# Neg5V0Reg.net
KiCad netlist of a schematic drawn in Altium Designer
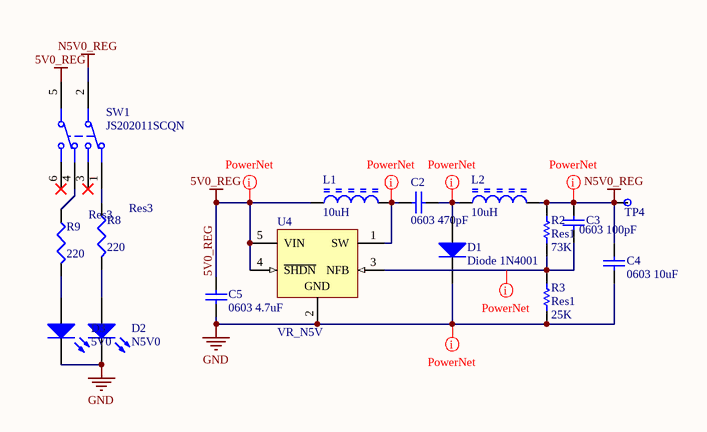
[diagram p0: Neg5V0Reg.SchDoc]

(export (version "E")
  (design (tool "Eeschema 10.0.6"))
  (components
    (comp (ref "C2")
      (value "0603 470pF")
      (footprint "CAPC1608X90X35LL10T15")
      (fields (field (name "PART NUMBER") "GRM188R61E475KE11D") (field (name "MANUFACTURER") "Murata"))
      (libsource (lib "Altium Content Vault") (part "CAP"))
    )
    (comp (ref "C3")
      (value "0603 100pF")
      (footprint "CAPC1608X90X35LL10T15")
      (fields (field (name "PART NUMBER") "GRM188R61E475KE11D") (field (name "MANUFACTURER") "Murata"))
      (libsource (lib "Altium Content Vault") (part "CAP"))
    )
    (comp (ref "C4")
      (value "0603 10uF")
      (footprint "CAPC1608X90X35LL10T15")
      (fields (field (name "PART NUMBER") "GRM188R61E475KE11D") (field (name "MANUFACTURER") "Murata"))
      (libsource (lib "Altium Content Vault") (part "CAP"))
    )
    (comp (ref "C5")
      (value "0603 4.7uF")
      (footprint "CAPC1608X90X35LL10T15")
      (fields (field (name "PART NUMBER") "GRM188R61E475KE11D") (field (name "MANUFACTURER") "Murata"))
      (libsource (lib "Altium Content Vault") (part "CAP"))
    )
    (comp (ref "D1")
      (value "Diode 1N4001")
      (footprint "DO-41")
      (description "1 Amp General Purpose Rectifier")
      (fields (field (name "PUBLISHER") "Altium Limited"))
      (libsource (lib "Miscellaneous Devices") (part "Diode 1N4001"))
    )
    (comp (ref "D2")
      (value "N5V0")
      (footprint "LTST-C171TBKT")
      (libsource (lib "RSX_Diodes") (part "Blue LED"))
    )
    (comp (ref "D3")
      (value "5V0")
      (footprint "LTST-C171TBKT")
      (libsource (lib "RSX_Diodes") (part "Blue LED"))
    )
    (comp (ref "L1")
      (value "10uH")
      (footprint "BOUR-CM322522_V")
      (description "Chip Inductor\r\n, 10 uH, +/- 10%, -40 to 125 degC, 1210 (3225 Metric), RoHS, Tape and Reel")
      (libsource (lib "Altium Content Vault") (part "BOUR-IND-2A"))
    )
    (comp (ref "L2")
      (value "10uH")
      (footprint "BOUR-CM322522_V")
      (description "Chip Inductor\r\n, 10 uH, +/- 10%, -40 to 125 degC, 1210 (3225 Metric), RoHS, Tape and Reel")
      (libsource (lib "Altium Content Vault") (part "BOUR-IND-2A"))
    )
    (comp (ref "R2")
      (value "Res1")
      (footprint "RESC1608X06N_0603")
      (description "Resistor")
      (fields (field (name "ALTIUM_VALUE") "73K") (field (name "PUBLISHER") "Altium Limited"))
      (libsource (lib "RSX_Resistors") (part "Res1"))
    )
    (comp (ref "R3")
      (value "Res1")
      (footprint "RESC1608X06N_0603")
      (description "Resistor")
      (fields (field (name "ALTIUM_VALUE") "25K") (field (name "PUBLISHER") "Altium Limited"))
      (libsource (lib "RSX_Resistors") (part "Res1"))
    )
    (comp (ref "R8")
      (value "Res3")
      (footprint "RESC1608X06N_0603")
      (description "Resistor")
      (fields (field (name "ALTIUM_VALUE") "220") (field (name "PUBLISHER") "Altium Limited"))
      (libsource (lib "RSX_Resistors") (part "Res3"))
    )
    (comp (ref "R9")
      (value "Res3")
      (footprint "RESC1608X06N_0603")
      (description "Resistor")
      (fields (field (name "ALTIUM_VALUE") "220") (field (name "PUBLISHER") "Altium Limited"))
      (libsource (lib "RSX_Resistors") (part "Res3"))
    )
    (comp (ref "SW1")
      (value "JS202011SCQN")
      (footprint "CKCP-JS202011SCQN-6_V")
      (description "Switch Slide DPDT, 0.3 A, 6 V, -40 to 85 degC, 6-Pin SMD, RoHS, Tape and Reel")
      (fields (field (name "MANUFACTURER") "C&K Components"))
      (libsource (lib "Altium Content Vault") (part "CKCP-JS202011SCQN-6"))
    )
    (comp (ref "TP4")
      (value "N5V0_REG")
      (footprint "50_MIL_PAD")
      (libsource (lib "RSX_Test_Points") (part "TestPt"))
    )
    (comp (ref "U4")
      (value "VR_N5V")
      (footprint "LT-S5-5-SOT-23_L")
      (fields
        (field (name "PARTNUMBER") "LT1617ES5#TRMPBF")
        (field (name "MANUFACTURER") "Linear Technology")
      )
      (libsource (lib "Altium Content Vault") (part "LT-LT161X_1931-S5-5"))
    )
  )
  (nets
    (net (code "1") (name "5V0_REG") (class "Default")
      (node (ref "C5") (pin "2") (pinfunction "2_2") (pintype "passive"))
      (node (ref "L1") (pin "1") (pinfunction "1_1") (pintype "passive"))
      (node (ref "SW1") (pin "5") (pinfunction "COM_5") (pintype "passive"))
      (node (ref "U4") (pin "4") (pinfunction "~{SHDN}_4") (pintype "input"))
      (node (ref "U4") (pin "5") (pinfunction "VIN_5") (pintype "power_in"))
    )
    (net (code "2") (name "GND") (class "Default")
      (node (ref "C4") (pin "1") (pinfunction "1_1") (pintype "passive"))
      (node (ref "C5") (pin "1") (pinfunction "1_1") (pintype "passive"))
      (node (ref "D1") (pin "2") (pinfunction "K_2") (pintype "passive"))
      (node (ref "D2") (pin "2") (pinfunction "K_2") (pintype "passive"))
      (node (ref "D3") (pin "2") (pinfunction "K_2") (pintype "passive"))
      (node (ref "R3") (pin "1") (pinfunction "1_1") (pintype "passive"))
      (node (ref "U4") (pin "2") (pinfunction "GND_2") (pintype "power_in"))
    )
    (net (code "3") (name "N5V0_REG") (class "Default")
      (node (ref "C3") (pin "2") (pinfunction "2_2") (pintype "passive"))
      (node (ref "C4") (pin "2") (pinfunction "2_2") (pintype "passive"))
      (node (ref "L2") (pin "2") (pinfunction "2_2") (pintype "passive"))
      (node (ref "R2") (pin "2") (pinfunction "2_2") (pintype "passive"))
      (node (ref "SW1") (pin "2") (pinfunction "COM_2") (pintype "passive"))
      (node (ref "TP4") (pin "1") (pinfunction "1_1") (pintype "passive"))
    )
    (net (code "4") (name "Net-(D1-A)") (class "Default")
      (node (ref "C2") (pin "2") (pinfunction "2_2") (pintype "passive"))
      (node (ref "D1") (pin "1") (pinfunction "A_1") (pintype "passive"))
      (node (ref "L2") (pin "1") (pinfunction "1_1") (pintype "passive"))
    )
    (net (code "5") (name "Net-(D2-A)") (class "Default")
      (node (ref "D2") (pin "1") (pinfunction "A_1") (pintype "passive"))
      (node (ref "R8") (pin "2") (pinfunction "2_2") (pintype "passive"))
    )
    (net (code "6") (name "Net-(D3-A)") (class "Default")
      (node (ref "D3") (pin "1") (pinfunction "A_1") (pintype "passive"))
      (node (ref "R9") (pin "2") (pinfunction "2_2") (pintype "passive"))
    )
    (net (code "7") (name "Net-(R8-Pad1)") (class "Default")
      (node (ref "R8") (pin "1") (pinfunction "1_1") (pintype "passive"))
      (node (ref "SW1") (pin "1") (pinfunction "1_1") (pintype "passive"))
    )
    (net (code "8") (name "Net-(R9-Pad1)") (class "Default")
      (node (ref "R9") (pin "1") (pinfunction "1_1") (pintype "passive"))
      (node (ref "SW1") (pin "4") (pinfunction "4_4") (pintype "passive"))
    )
    (net (code "9") (name "Net-(U4-NFB)") (class "Default")
      (node (ref "C3") (pin "1") (pinfunction "1_1") (pintype "passive"))
      (node (ref "R2") (pin "1") (pinfunction "1_1") (pintype "passive"))
      (node (ref "R3") (pin "2") (pinfunction "2_2") (pintype "passive"))
      (node (ref "U4") (pin "3") (pinfunction "NFB_3") (pintype "input"))
    )
    (net (code "10") (name "Net-(U4-SW)") (class "Default")
      (node (ref "C2") (pin "1") (pinfunction "1_1") (pintype "passive"))
      (node (ref "L1") (pin "2") (pinfunction "2_2") (pintype "passive"))
      (node (ref "U4") (pin "1") (pinfunction "SW_1") (pintype "power_in"))
    )
    (net (code "11") (name "unconnected-(SW1-Pad3)") (class "Default")
      (node (ref "SW1") (pin "3") (pinfunction "3_3") (pintype "passive+no_connect"))
    )
    (net (code "12") (name "unconnected-(SW1-Pad6)") (class "Default")
      (node (ref "SW1") (pin "6") (pinfunction "6_6") (pintype "passive+no_connect"))
    )
  )
)
